# Nguyen_Quang_Minh.net
KiCad netlist of a schematic drawn in Altium Designer
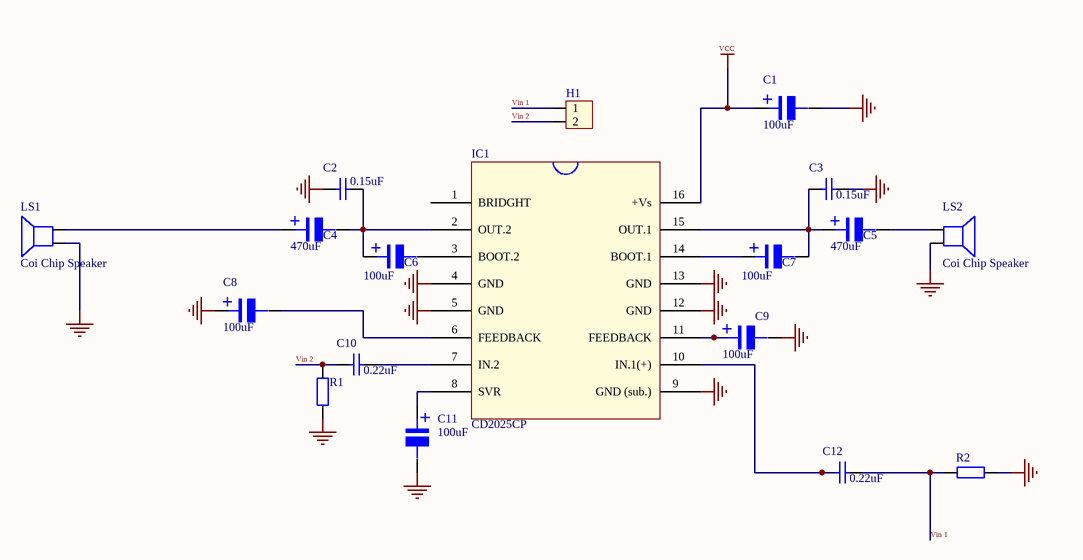
[diagram p0: Nguyen Quang Minh.SchDoc]

(export (version "E")
  (design (tool "Eeschema 10.0.6"))
  (components
    (comp (ref "C1")
      (value "100uF")
      (footprint "tu nhom 8 (f)")
      (description "Dán")
      (libsource (lib "Tu dien") (part "Tu Nhom 100uF 50V"))
    )
    (comp (ref "C2")
      (value "0.15uF")
      (footprint "tu gom")
      (description "Cắm")
      (libsource (lib "Tu dien") (part "Tu gom 15pF 50V"))
    )
    (comp (ref "C3")
      (value "0.15uF")
      (footprint "tu gom")
      (description "Cắm")
      (libsource (lib "Tu dien") (part "Tu gom 15pF 50V"))
    )
    (comp (ref "C4")
      (value "470uF")
      (footprint "tu nhom 10 (G)")
      (description "Dán")
      (libsource (lib "Tu dien") (part "Tu Nhom 470uF 35V"))
    )
    (comp (ref "C5")
      (value "470uF")
      (footprint "tu nhom 10 (G)")
      (description "Dán")
      (libsource (lib "Tu dien") (part "Tu Nhom 470uF 35V"))
    )
    (comp (ref "C6")
      (value "100uF")
      (footprint "tu nhom 8 (f)")
      (description "Dán")
      (libsource (lib "Tu dien") (part "Tu Nhom 100uF 50V"))
    )
    (comp (ref "C7")
      (value "100uF")
      (footprint "tu nhom 8 (f)")
      (description "Dán")
      (libsource (lib "Tu dien") (part "Tu Nhom 100uF 50V"))
    )
    (comp (ref "C8")
      (value "100uF")
      (footprint "tu nhom 8 (f)")
      (description "Dán")
      (libsource (lib "Tu dien") (part "Tu Nhom 100uF 50V"))
    )
    (comp (ref "C9")
      (value "100uF")
      (footprint "tu nhom 8 (f)")
      (description "Dán")
      (libsource (lib "Tu dien") (part "Tu Nhom 100uF 50V"))
    )
    (comp (ref "C10")
      (value "0.22uF")
      (footprint "tu gom")
      (description "Cắm")
      (libsource (lib "Tu dien") (part "Tu gom 15pF 50V"))
    )
    (comp (ref "C11")
      (value "100uF")
      (footprint "tu nhom 8 (f)")
      (description "Dán")
      (libsource (lib "") (part "Tu Nhom 100uF 50V_1"))
    )
    (comp (ref "C12")
      (value "0.22uF")
      (footprint "tu gom")
      (description "Cắm")
      (libsource (lib "Tu dien") (part "Tu gom 15pF 50V"))
    )
    (comp (ref "H1")
      (value "Header 2P 2.54 Duc Cong")
      (footprint "Header 2P DC 2.54")
      (description "Cắm")
      (libsource (lib "Header") (part "Header 2P 2.54 Duc Cong"))
    )
    (comp (ref "IC1")
      (value "CD2025CP")
      (footprint "CD2025CP")
      (libsource (lib "Nguyen Quang Minh") (part "CD2025CP"))
    )
    (comp (ref "LS1")
      (value "Coi Chip Speaker")
      (footprint "Coi Chip Speacker")
      (description "Còi chip")
      (libsource (lib "Component") (part "Coi Chip Speaker"))
    )
    (comp (ref "LS2")
      (value "Coi Chip Speaker")
      (footprint "Coi Chip Speacker")
      (description "Còi chip")
      (libsource (lib "Component") (part "Coi Chip Speaker"))
    )
    (comp (ref "R1")
      (value "1k")
      (footprint "tro smd 0603")
      (description "Dán")
      (libsource (lib "Dien Tro") (part "Tro 0603 1% 1k"))
    )
    (comp (ref "R2")
      (value "1k")
      (footprint "tro smd 0603")
      (description "Dán")
      (libsource (lib "Dien Tro") (part "Tro 0603 1% 1k"))
    )
  )
  (nets
    (net (code "1") (name "/Vin 1") (class "Default")
      (node (ref "C12") (pin "1") (pinfunction "1_1") (pintype "passive"))
      (node (ref "H1") (pin "1") (pinfunction "1_1") (pintype "passive"))
      (node (ref "R2") (pin "1") (pinfunction "1_1") (pintype "passive"))
    )
    (net (code "2") (name "/Vin 2") (class "Default")
      (node (ref "C10") (pin "2") (pinfunction "2_2") (pintype "passive"))
      (node (ref "H1") (pin "2") (pinfunction "2_2") (pintype "passive"))
      (node (ref "R1") (pin "2") (pinfunction "2_2") (pintype "passive"))
    )
    (net (code "3") (name "GND") (class "Default")
      (node (ref "C1") (pin "2") (pinfunction "2_2") (pintype "passive"))
      (node (ref "C11") (pin "2") (pinfunction "2_2") (pintype "passive"))
      (node (ref "C2") (pin "2") (pinfunction "2_2") (pintype "passive"))
      (node (ref "C3") (pin "1") (pinfunction "1_1") (pintype "passive"))
      (node (ref "C8") (pin "1") (pinfunction "1_1") (pintype "passive"))
      (node (ref "C9") (pin "2") (pinfunction "2_2") (pintype "passive"))
      (node (ref "IC1") (pin "12") (pinfunction "GND_12") (pintype "passive"))
      (node (ref "IC1") (pin "13") (pinfunction "GND_13") (pintype "passive"))
      (node (ref "IC1") (pin "4") (pinfunction "GND_4") (pintype "passive"))
      (node (ref "IC1") (pin "5") (pinfunction "GND_5") (pintype "passive"))
      (node (ref "IC1") (pin "9") (pinfunction "GND_(sub.)_9") (pintype "passive"))
      (node (ref "LS1") (pin "1") (pinfunction "1_1") (pintype "passive"))
      (node (ref "LS2") (pin "2") (pinfunction "2_2") (pintype "passive"))
      (node (ref "R1") (pin "1") (pinfunction "1_1") (pintype "passive"))
      (node (ref "R2") (pin "2") (pinfunction "2_2") (pintype "passive"))
    )
    (net (code "4") (name "Net-(C4-Pad1)") (class "Default")
      (node (ref "C4") (pin "1") (pinfunction "1_1") (pintype "passive"))
      (node (ref "LS1") (pin "2") (pinfunction "2_2") (pintype "passive"))
    )
    (net (code "5") (name "Net-(C5-Pad2)") (class "Default")
      (node (ref "C5") (pin "2") (pinfunction "2_2") (pintype "passive"))
      (node (ref "LS2") (pin "1") (pinfunction "1_1") (pintype "passive"))
    )
    (net (code "6") (name "Net-(C8-Pad2)") (class "Default")
      (node (ref "C8") (pin "2") (pinfunction "2_2") (pintype "passive"))
      (node (ref "IC1") (pin "6") (pinfunction "FEEDBACK_6") (pintype "passive"))
    )
    (net (code "7") (name "Net-(C9-Pad1)") (class "Default")
      (node (ref "C9") (pin "1") (pinfunction "1_1") (pintype "passive"))
      (node (ref "IC1") (pin "11") (pinfunction "FEEDBACK_11") (pintype "passive"))
    )
    (net (code "8") (name "Net-(IC1-BOOT.1)") (class "Default")
      (node (ref "C7") (pin "1") (pinfunction "1_1") (pintype "passive"))
      (node (ref "IC1") (pin "14") (pinfunction "BOOT.1_14") (pintype "passive"))
    )
    (net (code "9") (name "Net-(IC1-BOOT.2)") (class "Default")
      (node (ref "C6") (pin "2") (pinfunction "2_2") (pintype "passive"))
      (node (ref "IC1") (pin "3") (pinfunction "BOOT.2_3") (pintype "passive"))
    )
    (net (code "10") (name "Net-(IC1-IN.1(+))") (class "Default")
      (node (ref "C12") (pin "2") (pinfunction "2_2") (pintype "passive"))
      (node (ref "IC1") (pin "10") (pinfunction "IN.1(+)_10") (pintype "passive"))
    )
    (net (code "11") (name "Net-(IC1-IN.2)") (class "Default")
      (node (ref "C10") (pin "1") (pinfunction "1_1") (pintype "passive"))
      (node (ref "IC1") (pin "7") (pinfunction "IN.2_7") (pintype "passive"))
    )
    (net (code "12") (name "Net-(IC1-OUT.1)") (class "Default")
      (node (ref "C3") (pin "2") (pinfunction "2_2") (pintype "passive"))
      (node (ref "C5") (pin "1") (pinfunction "1_1") (pintype "passive"))
      (node (ref "C7") (pin "2") (pinfunction "2_2") (pintype "passive"))
      (node (ref "IC1") (pin "15") (pinfunction "OUT.1_15") (pintype "passive"))
    )
    (net (code "13") (name "Net-(IC1-OUT.2)") (class "Default")
      (node (ref "C2") (pin "1") (pinfunction "1_1") (pintype "passive"))
      (node (ref "C4") (pin "2") (pinfunction "2_2") (pintype "passive"))
      (node (ref "C6") (pin "1") (pinfunction "1_1") (pintype "passive"))
      (node (ref "IC1") (pin "2") (pinfunction "OUT.2_2") (pintype "passive"))
    )
    (net (code "14") (name "Net-(IC1-SVR)") (class "Default")
      (node (ref "C11") (pin "1") (pinfunction "1_1") (pintype "passive"))
      (node (ref "IC1") (pin "8") (pinfunction "SVR_8") (pintype "passive"))
    )
    (net (code "15") (name "VCC") (class "Default")
      (node (ref "C1") (pin "1") (pinfunction "1_1") (pintype "passive"))
      (node (ref "IC1") (pin "16") (pinfunction "+Vs_16") (pintype "passive"))
    )
    (net (code "16") (name "unconnected-(IC1-BRIDGHT-Pad1)") (class "Default")
      (node (ref "IC1") (pin "1") (pinfunction "BRIDGHT_1") (pintype "passive"))
    )
  )
)
